# 3_MCU.net
KiCad netlist of a schematic drawn in Altium Designer
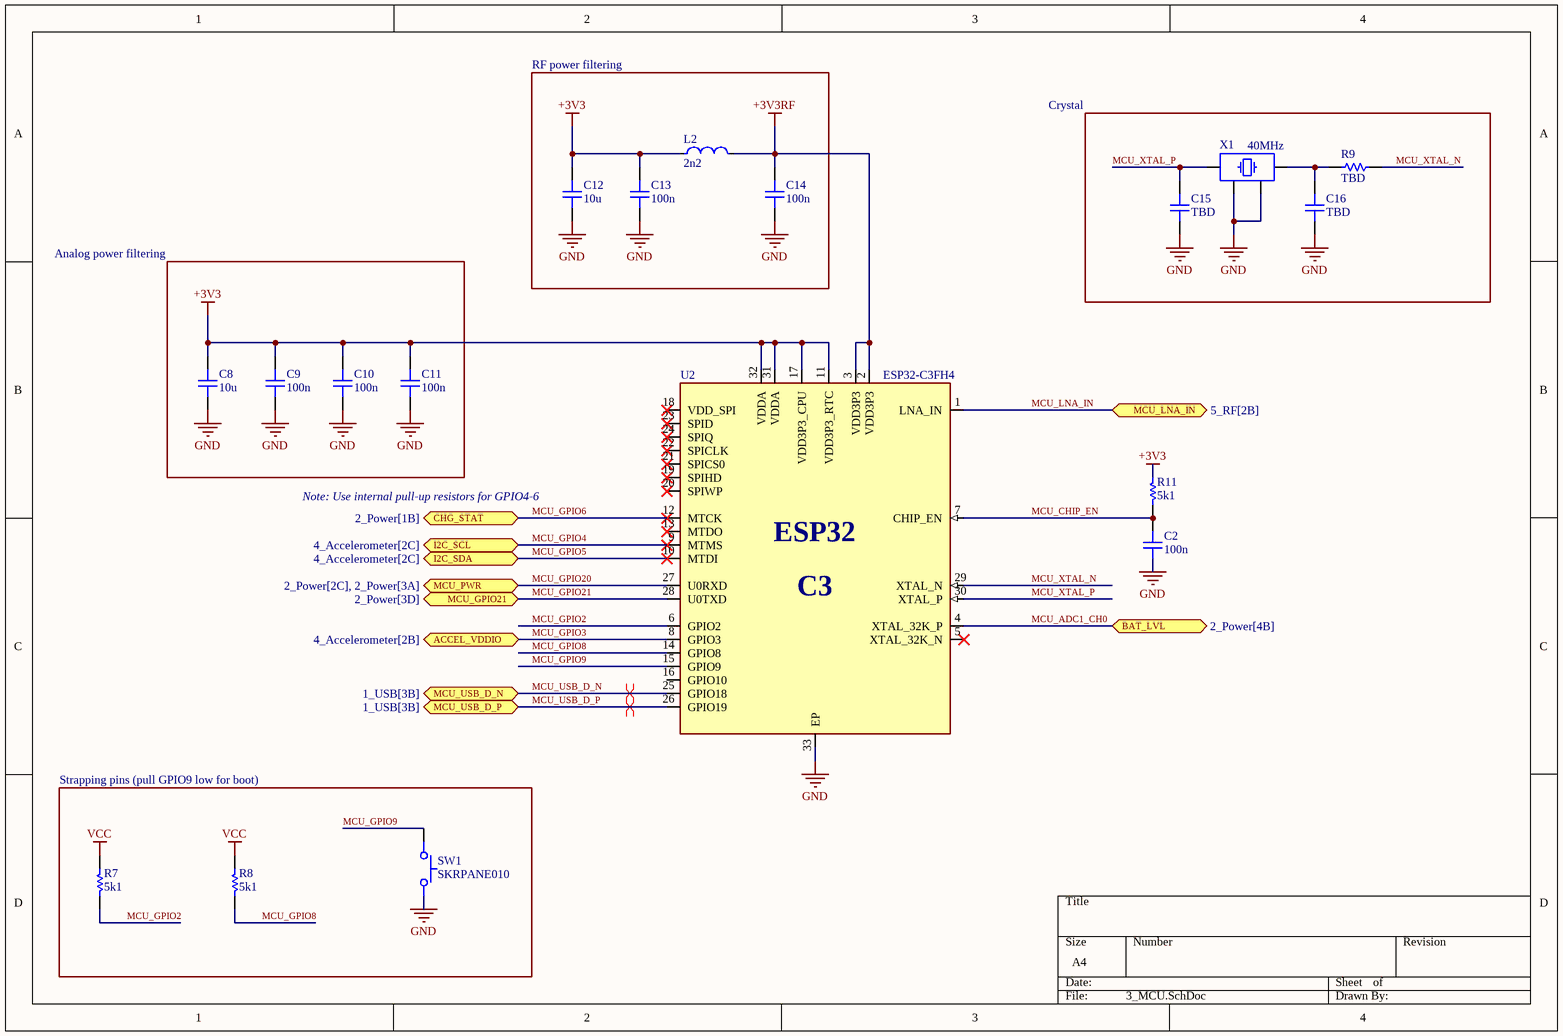
[diagram p0: 3_MCU.SchDoc]

(export (version "E")
  (design (tool "Eeschema 10.0.6"))
  (components
    (comp (ref "C2")
      (value "100n")
      (footprint "CAP_0402")
      (description "Capacitor SMD 0402 16V")
      (libsource (lib "Schematic-Lib-PhilsLab") (part "CAP_0402_16V"))
    )
    (comp (ref "C8")
      (value "10u")
      (footprint "CAP_0402")
      (description "Capacitor SMD 0402 10V")
      (libsource (lib "Schematic-Lib-PhilsLab") (part "CAP_0402_10V"))
    )
    (comp (ref "C9")
      (value "100n")
      (footprint "CAP_0402")
      (description "Capacitor SMD 0402 16V")
      (libsource (lib "Schematic-Lib-PhilsLab") (part "CAP_0402_16V"))
    )
    (comp (ref "C10")
      (value "100n")
      (footprint "CAP_0402")
      (description "Capacitor SMD 0402 16V")
      (libsource (lib "Schematic-Lib-PhilsLab") (part "CAP_0402_16V"))
    )
    (comp (ref "C11")
      (value "100n")
      (footprint "CAP_0402")
      (description "Capacitor SMD 0402 16V")
      (libsource (lib "Schematic-Lib-PhilsLab") (part "CAP_0402_16V"))
    )
    (comp (ref "C12")
      (value "10u")
      (footprint "CAP_0402")
      (description "Capacitor SMD 0402 10V")
      (libsource (lib "Schematic-Lib-PhilsLab") (part "CAP_0402_10V"))
    )
    (comp (ref "C13")
      (value "100n")
      (footprint "CAP_0402")
      (description "Capacitor SMD 0402 16V")
      (libsource (lib "Schematic-Lib-PhilsLab") (part "CAP_0402_16V"))
    )
    (comp (ref "C14")
      (value "100n")
      (footprint "CAP_0402")
      (description "Capacitor SMD 0402 16V")
      (libsource (lib "Schematic-Lib-PhilsLab") (part "CAP_0402_16V"))
    )
    (comp (ref "C15")
      (value "TBD")
      (footprint "CAP_0402")
      (description "Capacitor SMD 0402 10V")
      (libsource (lib "Schematic-Lib-PhilsLab") (part "CAP_0402_10V"))
    )
    (comp (ref "C16")
      (value "TBD")
      (footprint "CAP_0402")
      (description "Capacitor SMD 0402 10V")
      (libsource (lib "Schematic-Lib-PhilsLab") (part "CAP_0402_10V"))
    )
    (comp (ref "L2")
      (value "2n2")
      (footprint "FP-LQW15AN_80-MFG")
      (description "Wire Wound RF Inductor 2.2nH ±2% 2530mA 0.022Ω 0402 (1005)")
      (libsource (lib "Altium Content Vault") (part "725321dda6339637d4d059423bc1c3c"))
    )
    (comp (ref "R7")
      (value "5k1")
      (footprint "RESC1005X40X25ML10T10")
      (fields (field (name "PART NUMBER") "RK73B1ETTP512J") (field (name "MANUFACTURER") "KOA Speer"))
      (libsource (lib "Altium Content Vault") (part "RES"))
    )
    (comp (ref "R8")
      (value "5k1")
      (footprint "RESC1005X40X25ML10T10")
      (fields (field (name "PART NUMBER") "RK73B1ETTP512J") (field (name "MANUFACTURER") "KOA Speer"))
      (libsource (lib "Altium Content Vault") (part "RES"))
    )
    (comp (ref "R9")
      (value "TBD")
      (footprint "RES_0402")
      (description "Resistor SMD 0402")
      (libsource (lib "Schematic-Lib-PhilsLab") (part "RES_0402"))
    )
    (comp (ref "R11")
      (value "5k1")
      (footprint "RESC1005X40X25ML10T10")
      (fields (field (name "PART NUMBER") "RK73B1ETTP512J") (field (name "MANUFACTURER") "KOA Speer"))
      (libsource (lib "Altium Content Vault") (part "RES"))
    )
    (comp (ref "SW1")
      (value "SKRPANE010")
      (footprint "SKRPANE010")
      (description "Tactile Switch SMD SPST")
      (fields (field (name "MANUFACTURER") "Alps Alpine"))
      (libsource (lib "Schematic-Lib-PhilsLab") (part "SKRPANE010"))
    )
    (comp (ref "U2")
      (value "ESP32-C3FH4")
      (footprint "QFN32-5x5")
      (fields (field (name "MANUFACTURER") "Espressif") (field (name "MANUFACTURER PART NUMBER") "ESP32-C3"))
      (libsource (lib "Schematic-Lib-PhilsLab") (part "ESP32-C3"))
    )
    (comp (ref "X1")
      (value "40MHz")
      (footprint "XTAL_2520")
      (description "Crystal SMD 2520")
      (libsource (lib "Schematic-Lib-PhilsLab") (part "XTAL_2520"))
    )
  )
  (nets
    (net (code "1") (name "+3V3") (class "Default")
      (node (ref "C10") (pin "2") (pinfunction "2_2") (pintype "passive"))
      (node (ref "C11") (pin "2") (pinfunction "2_2") (pintype "passive"))
      (node (ref "C12") (pin "2") (pinfunction "2_2") (pintype "passive"))
      (node (ref "C13") (pin "2") (pinfunction "2_2") (pintype "passive"))
      (node (ref "C8") (pin "2") (pinfunction "2_2") (pintype "passive"))
      (node (ref "C9") (pin "2") (pinfunction "2_2") (pintype "passive"))
      (node (ref "L2") (pin "1") (pinfunction "1_1") (pintype "passive"))
      (node (ref "R11") (pin "1") (pinfunction "1_1") (pintype "passive"))
      (node (ref "U2") (pin "11") (pinfunction "VDD3P3_RTC_11") (pintype "power_in"))
      (node (ref "U2") (pin "17") (pinfunction "VDD3P3_CPU_17") (pintype "power_in"))
      (node (ref "U2") (pin "31") (pinfunction "VDDA_31") (pintype "power_in"))
      (node (ref "U2") (pin "32") (pinfunction "VDDA_32") (pintype "power_in"))
    )
    (net (code "2") (name "+3V3RF") (class "Default")
      (node (ref "C14") (pin "2") (pinfunction "2_2") (pintype "passive"))
      (node (ref "L2") (pin "2") (pinfunction "2_2") (pintype "passive"))
      (node (ref "U2") (pin "2") (pinfunction "VDD3P3_2") (pintype "power_in"))
      (node (ref "U2") (pin "3") (pinfunction "VDD3P3_3") (pintype "power_in"))
    )
    (net (code "3") (name "/MCU_ADC1_CH0") (class "Default")
      (node (ref "U2") (pin "4") (pinfunction "XTAL_32K_P_4") (pintype "bidirectional"))
    )
    (net (code "4") (name "/MCU_CHIP_EN") (class "Default")
      (node (ref "C2") (pin "1") (pinfunction "1_1") (pintype "passive"))
      (node (ref "R11") (pin "2") (pinfunction "2_2") (pintype "passive"))
      (node (ref "U2") (pin "7") (pinfunction "CHIP_EN_7") (pintype "input"))
    )
    (net (code "5") (name "/MCU_GPIO2") (class "Default")
      (node (ref "R7") (pin "1") (pinfunction "1_1") (pintype "passive"))
      (node (ref "U2") (pin "6") (pinfunction "GPIO2_6") (pintype "bidirectional"))
    )
    (net (code "6") (name "/MCU_GPIO3") (class "Default")
      (node (ref "U2") (pin "8") (pinfunction "GPIO3_8") (pintype "bidirectional"))
    )
    (net (code "7") (name "/MCU_GPIO4") (class "Default")
      (node (ref "U2") (pin "9") (pinfunction "MTMS_9") (pintype "bidirectional+no_connect"))
    )
    (net (code "8") (name "/MCU_GPIO5") (class "Default")
      (node (ref "U2") (pin "10") (pinfunction "MTDI_10") (pintype "bidirectional+no_connect"))
    )
    (net (code "9") (name "/MCU_GPIO6") (class "Default")
      (node (ref "U2") (pin "12") (pinfunction "MTCK_12") (pintype "bidirectional+no_connect"))
    )
    (net (code "10") (name "/MCU_GPIO8") (class "Default")
      (node (ref "R8") (pin "1") (pinfunction "1_1") (pintype "passive"))
      (node (ref "U2") (pin "14") (pinfunction "GPIO8_14") (pintype "bidirectional"))
    )
    (net (code "11") (name "/MCU_GPIO9") (class "Default")
      (node (ref "SW1") (pin "34") (pintype "passive"))
      (node (ref "U2") (pin "15") (pinfunction "GPIO9_15") (pintype "bidirectional"))
    )
    (net (code "12") (name "/MCU_GPIO20") (class "Default")
      (node (ref "U2") (pin "27") (pinfunction "U0RXD_27") (pintype "bidirectional"))
    )
    (net (code "13") (name "/MCU_GPIO21") (class "Default")
      (node (ref "U2") (pin "28") (pinfunction "U0TXD_28") (pintype "bidirectional"))
    )
    (net (code "14") (name "/MCU_LNA_IN") (class "Default")
      (node (ref "U2") (pin "1") (pinfunction "LNA_IN_1") (pintype "bidirectional"))
    )
    (net (code "15") (name "/MCU_USB_D_N") (class "Default")
      (node (ref "U2") (pin "25") (pinfunction "GPIO18_25") (pintype "bidirectional"))
    )
    (net (code "16") (name "/MCU_USB_D_P") (class "Default")
      (node (ref "U2") (pin "26") (pinfunction "GPIO19_26") (pintype "bidirectional"))
    )
    (net (code "17") (name "/MCU_XTAL_N") (class "Default")
      (node (ref "R9") (pin "2") (pinfunction "2_2") (pintype "passive"))
      (node (ref "U2") (pin "29") (pinfunction "XTAL_N_29") (pintype "input"))
    )
    (net (code "18") (name "/MCU_XTAL_P") (class "Default")
      (node (ref "C15") (pin "2") (pinfunction "2_2") (pintype "passive"))
      (node (ref "U2") (pin "30") (pinfunction "XTAL_P_30") (pintype "input"))
      (node (ref "X1") (pin "1") (pinfunction "1_1") (pintype "passive"))
    )
    (net (code "19") (name "GND") (class "Default")
      (node (ref "C10") (pin "1") (pinfunction "1_1") (pintype "passive"))
      (node (ref "C11") (pin "1") (pinfunction "1_1") (pintype "passive"))
      (node (ref "C12") (pin "1") (pinfunction "1_1") (pintype "passive"))
      (node (ref "C13") (pin "1") (pinfunction "1_1") (pintype "passive"))
      (node (ref "C14") (pin "1") (pinfunction "1_1") (pintype "passive"))
      (node (ref "C15") (pin "1") (pinfunction "1_1") (pintype "passive"))
      (node (ref "C16") (pin "1") (pinfunction "1_1") (pintype "passive"))
      (node (ref "C2") (pin "2") (pinfunction "2_2") (pintype "passive"))
      (node (ref "C8") (pin "1") (pinfunction "1_1") (pintype "passive"))
      (node (ref "C9") (pin "1") (pinfunction "1_1") (pintype "passive"))
      (node (ref "SW1") (pin "12") (pintype "passive"))
      (node (ref "U2") (pin "33") (pinfunction "EP_33") (pintype "power_in"))
      (node (ref "X1") (pin "2") (pinfunction "2_2") (pintype "passive"))
      (node (ref "X1") (pin "4") (pinfunction "4_4") (pintype "passive"))
    )
    (net (code "20") (name "Net-(C16-Pad2)") (class "Default")
      (node (ref "C16") (pin "2") (pinfunction "2_2") (pintype "passive"))
      (node (ref "R9") (pin "1") (pinfunction "1_1") (pintype "passive"))
      (node (ref "X1") (pin "3") (pinfunction "3_3") (pintype "passive"))
    )
    (net (code "21") (name "VCC") (class "Default")
      (node (ref "R7") (pin "2") (pinfunction "2_2") (pintype "passive"))
      (node (ref "R8") (pin "2") (pinfunction "2_2") (pintype "passive"))
    )
    (net (code "22") (name "unconnected-(U2-GPIO10-Pad16)") (class "Default")
      (node (ref "U2") (pin "16") (pinfunction "GPIO10_16") (pintype "bidirectional"))
    )
    (net (code "23") (name "unconnected-(U2-MTDO-Pad13)") (class "Default")
      (node (ref "U2") (pin "13") (pinfunction "MTDO_13") (pintype "bidirectional+no_connect"))
    )
    (net (code "24") (name "unconnected-(U2-SPICLK-Pad22)") (class "Default")
      (node (ref "U2") (pin "22") (pinfunction "SPICLK_22") (pintype "bidirectional+no_connect"))
    )
    (net (code "25") (name "unconnected-(U2-SPICS0-Pad21)") (class "Default")
      (node (ref "U2") (pin "21") (pinfunction "SPICS0_21") (pintype "bidirectional+no_connect"))
    )
    (net (code "26") (name "unconnected-(U2-SPID-Pad23)") (class "Default")
      (node (ref "U2") (pin "23") (pinfunction "SPID_23") (pintype "bidirectional+no_connect"))
    )
    (net (code "27") (name "unconnected-(U2-SPIHD-Pad19)") (class "Default")
      (node (ref "U2") (pin "19") (pinfunction "SPIHD_19") (pintype "bidirectional+no_connect"))
    )
    (net (code "28") (name "unconnected-(U2-SPIQ-Pad24)") (class "Default")
      (node (ref "U2") (pin "24") (pinfunction "SPIQ_24") (pintype "bidirectional+no_connect"))
    )
    (net (code "29") (name "unconnected-(U2-SPIWP-Pad20)") (class "Default")
      (node (ref "U2") (pin "20") (pinfunction "SPIWP_20") (pintype "bidirectional+no_connect"))
    )
    (net (code "30") (name "unconnected-(U2-VDD_SPI-Pad18)") (class "Default")
      (node (ref "U2") (pin "18") (pinfunction "VDD_SPI_18") (pintype "power_in+no_connect"))
    )
    (net (code "31") (name "unconnected-(U2-XTAL_32K_N-Pad5)") (class "Default")
      (node (ref "U2") (pin "5") (pinfunction "XTAL_32K_N_5") (pintype "bidirectional+no_connect"))
    )
  )
)
